# wrover-cam1.net
KiCad netlist of a schematic drawn in EAGLE
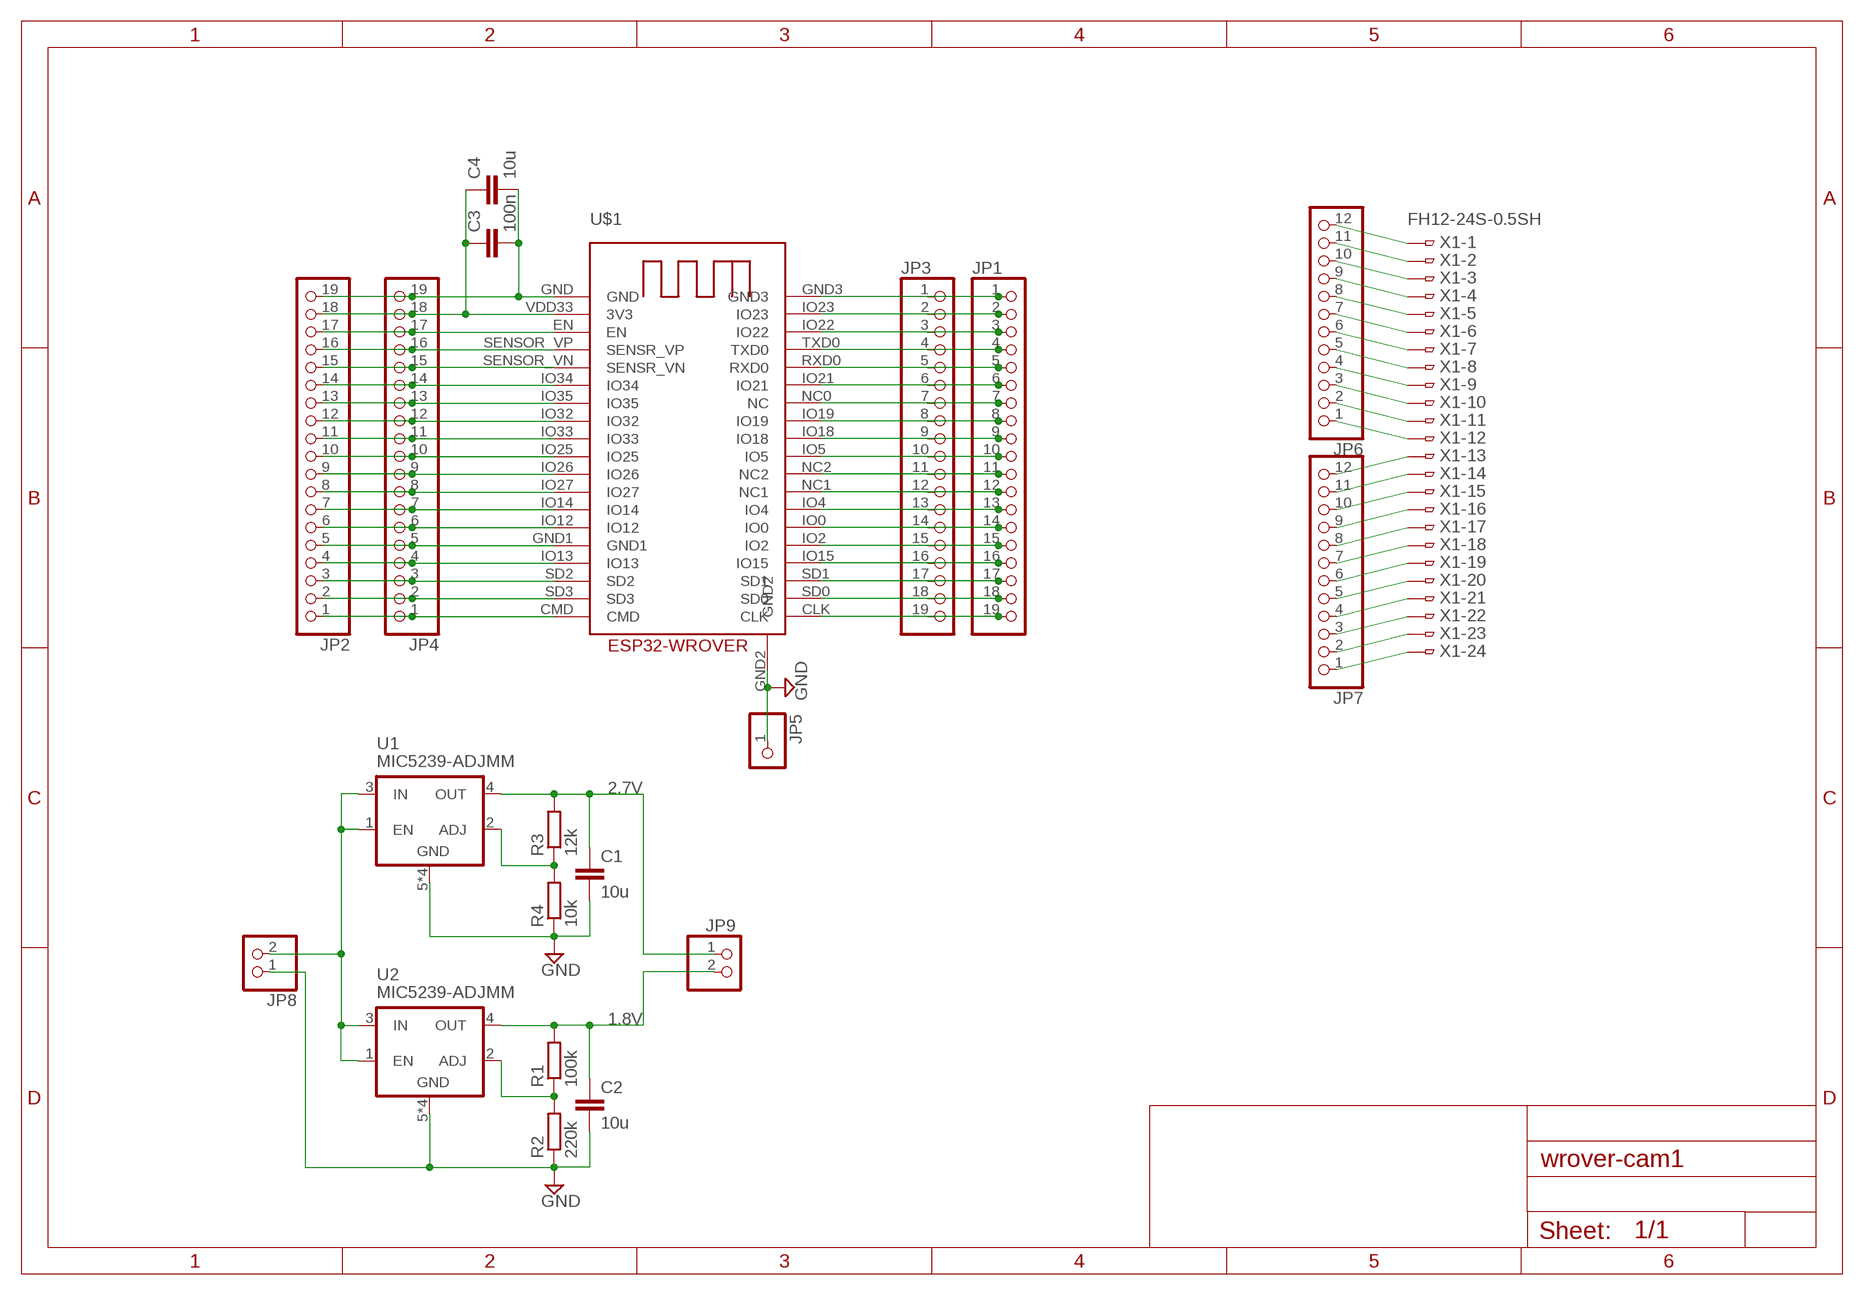
[diagram p0: schematic, sheet 1]

(export (version "E")
  (design (tool "Eeschema 10.0.6"))
  (components
    (comp (ref "C1")
      (value "10u")
      (footprint "eagle-import:C1210K")
      (libsource (lib "eagle-import") (part "C-EUC1210K"))
    )
    (comp (ref "C2")
      (value "10u")
      (footprint "eagle-import:C1210K")
      (libsource (lib "eagle-import") (part "C-EUC1210K"))
    )
    (comp (ref "C3")
      (value "100n")
      (footprint "eagle-import:C0805K")
      (libsource (lib "eagle-import") (part "C-EUC0805K"))
    )
    (comp (ref "C4")
      (value "10u")
      (footprint "eagle-import:C1210K")
      (libsource (lib "eagle-import") (part "C-EUC1210K"))
    )
    (comp (ref "JP1")
      (value "PINHD-1X19")
      (footprint "eagle-import:1X19")
      (libsource (lib "eagle-import") (part "PINHD-1X19"))
    )
    (comp (ref "JP2")
      (value "PINHD-1X19")
      (footprint "eagle-import:1X19")
      (libsource (lib "eagle-import") (part "PINHD-1X19"))
    )
    (comp (ref "JP3")
      (value "PINHD-1X19")
      (footprint "eagle-import:1X19")
      (libsource (lib "eagle-import") (part "PINHD-1X19"))
    )
    (comp (ref "JP4")
      (value "PINHD-1X19")
      (footprint "eagle-import:1X19")
      (libsource (lib "eagle-import") (part "PINHD-1X19"))
    )
    (comp (ref "JP5")
      (value "PINHD-1X1")
      (footprint "eagle-import:1X01")
      (libsource (lib "eagle-import") (part "PINHD-1X1"))
    )
    (comp (ref "JP6")
      (value "PINHD-1X12")
      (footprint "eagle-import:1X12")
      (libsource (lib "eagle-import") (part "PINHD-1X12"))
    )
    (comp (ref "JP7")
      (value "PINHD-1X12")
      (footprint "eagle-import:1X12")
      (libsource (lib "eagle-import") (part "PINHD-1X12"))
    )
    (comp (ref "JP8")
      (value "PINHD-1X2")
      (footprint "eagle-import:1X02")
      (libsource (lib "eagle-import") (part "PINHD-1X2"))
    )
    (comp (ref "JP9")
      (value "PINHD-1X2")
      (footprint "eagle-import:1X02")
      (libsource (lib "eagle-import") (part "PINHD-1X2"))
    )
    (comp (ref "R1")
      (value "100k")
      (footprint "eagle-import:R1206")
      (libsource (lib "eagle-import") (part "R-EU_R1206"))
    )
    (comp (ref "R2")
      (value "220k")
      (footprint "eagle-import:R1206")
      (libsource (lib "eagle-import") (part "R-EU_R1206"))
    )
    (comp (ref "R3")
      (value "12k")
      (footprint "eagle-import:R1206")
      (libsource (lib "eagle-import") (part "R-EU_R1206"))
    )
    (comp (ref "R4")
      (value "10k")
      (footprint "eagle-import:R1206")
      (libsource (lib "eagle-import") (part "R-EU_R1206"))
    )
    (comp (ref "U$1")
      (value "ESP32-WROVER")
      (footprint "eagle-import:ESP32-WROVER")
      (libsource (lib "eagle-import") (part "ESP32-WROVER"))
    )
    (comp (ref "U1")
      (value "MIC5239-ADJMM")
      (footprint "eagle-import:MSOP08")
      (libsource (lib "eagle-import") (part "MIC5239-ADJMM"))
    )
    (comp (ref "U2")
      (value "MIC5239-ADJMM")
      (footprint "eagle-import:MSOP08")
      (libsource (lib "eagle-import") (part "MIC5239-ADJMM"))
    )
    (comp (ref "X1")
      (value "FH12-24S-0.5SH")
      (footprint "eagle-import:FH12-24S-0.5SH")
      (fields (field (name "MPN") "FH12-24S-0.5SH(55)"))
      (libsource (lib "eagle-import") (part "FH12-24S-0.5SH"))
    )
  )
  (nets
    (net (code "1") (name "/1.8V") (class "Default")
      (node (ref "C2") (pin "1") (pinfunction "1_1") (pintype "passive"))
      (node (ref "JP9") (pin "2") (pinfunction "2_2") (pintype "passive"))
      (node (ref "R1") (pin "2") (pinfunction "2_2") (pintype "passive"))
      (node (ref "U2") (pin "4") (pinfunction "OUT_4") (pintype "passive"))
    )
    (net (code "2") (name "/2.7V") (class "Default")
      (node (ref "C1") (pin "1") (pinfunction "1_1") (pintype "passive"))
      (node (ref "JP9") (pin "1") (pinfunction "1_1") (pintype "passive"))
      (node (ref "R3") (pin "2") (pinfunction "2_2") (pintype "passive"))
      (node (ref "U1") (pin "4") (pinfunction "OUT_4") (pintype "passive"))
    )
    (net (code "3") (name "GND") (class "Default")
      (node (ref "C1") (pin "2") (pinfunction "2_2") (pintype "passive"))
      (node (ref "C2") (pin "2") (pinfunction "2_2") (pintype "passive"))
      (node (ref "JP5") (pin "1") (pinfunction "1_1") (pintype "passive"))
      (node (ref "JP8") (pin "1") (pinfunction "1_1") (pintype "passive"))
      (node (ref "R2") (pin "1") (pinfunction "1_1") (pintype "passive"))
      (node (ref "R4") (pin "1") (pinfunction "1_1") (pintype "passive"))
      (node (ref "U$1") (pin "GND2") (pinfunction "GND2_GND2") (pintype "bidirectional"))
      (node (ref "U1") (pin "5") (pinfunction "GND_5") (pintype "power_in"))
      (node (ref "U1") (pin "6") (pinfunction "GND_6") (pintype "power_in"))
      (node (ref "U1") (pin "7") (pinfunction "GND_7") (pintype "power_in"))
      (node (ref "U1") (pin "8") (pinfunction "GND_8") (pintype "power_in"))
      (node (ref "U2") (pin "5") (pinfunction "GND_5") (pintype "power_in"))
      (node (ref "U2") (pin "6") (pinfunction "GND_6") (pintype "power_in"))
      (node (ref "U2") (pin "7") (pinfunction "GND_7") (pintype "power_in"))
      (node (ref "U2") (pin "8") (pinfunction "GND_8") (pintype "power_in"))
    )
    (net (code "4") (name "Net-(C3-Pad2)") (class "Default")
      (node (ref "C3") (pin "2") (pinfunction "2_2") (pintype "passive"))
      (node (ref "C4") (pin "2") (pinfunction "2_2") (pintype "passive"))
      (node (ref "JP2") (pin "19") (pinfunction "19_19") (pintype "passive"))
      (node (ref "JP4") (pin "19") (pinfunction "19_19") (pintype "passive"))
      (node (ref "U$1") (pin "GND") (pinfunction "GND_GND") (pintype "bidirectional"))
    )
    (net (code "5") (name "Net-(JP1-Pad1)") (class "Default")
      (node (ref "JP1") (pin "1") (pinfunction "1_1") (pintype "passive"))
      (node (ref "JP3") (pin "1") (pinfunction "1_1") (pintype "passive"))
      (node (ref "U$1") (pin "GND3") (pinfunction "GND3_GND3") (pintype "bidirectional"))
    )
    (net (code "6") (name "Net-(JP1-Pad2)") (class "Default")
      (node (ref "JP1") (pin "2") (pinfunction "2_2") (pintype "passive"))
      (node (ref "JP3") (pin "2") (pinfunction "2_2") (pintype "passive"))
      (node (ref "U$1") (pin "IO23") (pinfunction "IO23_IO23") (pintype "bidirectional"))
    )
    (net (code "7") (name "Net-(JP1-Pad3)") (class "Default")
      (node (ref "JP1") (pin "3") (pinfunction "3_3") (pintype "passive"))
      (node (ref "JP3") (pin "3") (pinfunction "3_3") (pintype "passive"))
      (node (ref "U$1") (pin "IO22") (pinfunction "IO22_IO22") (pintype "bidirectional"))
    )
    (net (code "8") (name "Net-(JP1-Pad4)") (class "Default")
      (node (ref "JP1") (pin "4") (pinfunction "4_4") (pintype "passive"))
      (node (ref "JP3") (pin "4") (pinfunction "4_4") (pintype "passive"))
      (node (ref "U$1") (pin "TXD0") (pinfunction "TXD0_TXD0") (pintype "bidirectional"))
    )
    (net (code "9") (name "Net-(JP1-Pad5)") (class "Default")
      (node (ref "JP1") (pin "5") (pinfunction "5_5") (pintype "passive"))
      (node (ref "JP3") (pin "5") (pinfunction "5_5") (pintype "passive"))
      (node (ref "U$1") (pin "RXD0") (pinfunction "RXD0_RXD0") (pintype "bidirectional"))
    )
    (net (code "10") (name "Net-(JP1-Pad6)") (class "Default")
      (node (ref "JP1") (pin "6") (pinfunction "6_6") (pintype "passive"))
      (node (ref "JP3") (pin "6") (pinfunction "6_6") (pintype "passive"))
      (node (ref "U$1") (pin "IO21") (pinfunction "IO21_IO21") (pintype "bidirectional"))
    )
    (net (code "11") (name "Net-(JP1-Pad8)") (class "Default")
      (node (ref "JP1") (pin "8") (pinfunction "8_8") (pintype "passive"))
      (node (ref "JP3") (pin "8") (pinfunction "8_8") (pintype "passive"))
      (node (ref "U$1") (pin "IO19") (pinfunction "IO19_IO19") (pintype "bidirectional"))
    )
    (net (code "12") (name "Net-(JP1-Pad9)") (class "Default")
      (node (ref "JP1") (pin "9") (pinfunction "9_9") (pintype "passive"))
      (node (ref "JP3") (pin "9") (pinfunction "9_9") (pintype "passive"))
      (node (ref "U$1") (pin "IO18") (pinfunction "IO18_IO18") (pintype "bidirectional"))
    )
    (net (code "13") (name "Net-(JP1-Pad10)") (class "Default")
      (node (ref "JP1") (pin "10") (pinfunction "10_10") (pintype "passive"))
      (node (ref "JP3") (pin "10") (pinfunction "10_10") (pintype "passive"))
      (node (ref "U$1") (pin "IO5") (pinfunction "IO5_IO5") (pintype "bidirectional"))
    )
    (net (code "14") (name "Net-(JP1-Pad11)") (class "Default")
      (node (ref "JP1") (pin "11") (pinfunction "11_11") (pintype "passive"))
      (node (ref "JP3") (pin "11") (pinfunction "11_11") (pintype "passive"))
      (node (ref "U$1") (pin "NC2") (pinfunction "NC2_NC2") (pintype "bidirectional"))
    )
    (net (code "15") (name "Net-(JP1-Pad12)") (class "Default")
      (node (ref "JP1") (pin "12") (pinfunction "12_12") (pintype "passive"))
      (node (ref "JP3") (pin "12") (pinfunction "12_12") (pintype "passive"))
      (node (ref "U$1") (pin "NC1") (pinfunction "NC1_NC1") (pintype "bidirectional"))
    )
    (net (code "16") (name "Net-(JP1-Pad13)") (class "Default")
      (node (ref "JP1") (pin "13") (pinfunction "13_13") (pintype "passive"))
      (node (ref "JP3") (pin "13") (pinfunction "13_13") (pintype "passive"))
      (node (ref "U$1") (pin "IO4") (pinfunction "IO4_IO4") (pintype "bidirectional"))
    )
    (net (code "17") (name "Net-(JP1-Pad14)") (class "Default")
      (node (ref "JP1") (pin "14") (pinfunction "14_14") (pintype "passive"))
      (node (ref "JP3") (pin "14") (pinfunction "14_14") (pintype "passive"))
      (node (ref "U$1") (pin "IO0") (pinfunction "IO0_IO0") (pintype "bidirectional"))
    )
    (net (code "18") (name "Net-(JP1-Pad15)") (class "Default")
      (node (ref "JP1") (pin "15") (pinfunction "15_15") (pintype "passive"))
      (node (ref "JP3") (pin "15") (pinfunction "15_15") (pintype "passive"))
      (node (ref "U$1") (pin "IO2") (pinfunction "IO2_IO2") (pintype "bidirectional"))
    )
    (net (code "19") (name "Net-(JP1-Pad16)") (class "Default")
      (node (ref "JP1") (pin "16") (pinfunction "16_16") (pintype "passive"))
      (node (ref "JP3") (pin "16") (pinfunction "16_16") (pintype "passive"))
      (node (ref "U$1") (pin "IO15") (pinfunction "IO15_IO15") (pintype "bidirectional"))
    )
    (net (code "20") (name "Net-(JP1-Pad17)") (class "Default")
      (node (ref "JP1") (pin "17") (pinfunction "17_17") (pintype "passive"))
      (node (ref "JP3") (pin "17") (pinfunction "17_17") (pintype "passive"))
      (node (ref "U$1") (pin "SD1") (pinfunction "SD1_SD1") (pintype "bidirectional"))
    )
    (net (code "21") (name "Net-(JP1-Pad18)") (class "Default")
      (node (ref "JP1") (pin "18") (pinfunction "18_18") (pintype "passive"))
      (node (ref "JP3") (pin "18") (pinfunction "18_18") (pintype "passive"))
      (node (ref "U$1") (pin "SD0") (pinfunction "SD0_SD0") (pintype "bidirectional"))
    )
    (net (code "22") (name "Net-(JP1-Pad19)") (class "Default")
      (node (ref "JP1") (pin "19") (pinfunction "19_19") (pintype "passive"))
      (node (ref "JP3") (pin "19") (pinfunction "19_19") (pintype "passive"))
      (node (ref "U$1") (pin "CLK") (pinfunction "CLK_CLK") (pintype "bidirectional"))
    )
    (net (code "23") (name "Net-(JP2-Pad1)") (class "Default")
      (node (ref "JP2") (pin "1") (pinfunction "1_1") (pintype "passive"))
      (node (ref "JP4") (pin "1") (pinfunction "1_1") (pintype "passive"))
      (node (ref "U$1") (pin "CMD") (pinfunction "CMD_CMD") (pintype "bidirectional"))
    )
    (net (code "24") (name "Net-(JP2-Pad2)") (class "Default")
      (node (ref "JP2") (pin "2") (pinfunction "2_2") (pintype "passive"))
      (node (ref "JP4") (pin "2") (pinfunction "2_2") (pintype "passive"))
      (node (ref "U$1") (pin "SD3") (pinfunction "SD3_SD3") (pintype "bidirectional"))
    )
    (net (code "25") (name "Net-(JP2-Pad3)") (class "Default")
      (node (ref "JP2") (pin "3") (pinfunction "3_3") (pintype "passive"))
      (node (ref "JP4") (pin "3") (pinfunction "3_3") (pintype "passive"))
      (node (ref "U$1") (pin "SD2") (pinfunction "SD2_SD2") (pintype "bidirectional"))
    )
    (net (code "26") (name "Net-(JP2-Pad4)") (class "Default")
      (node (ref "JP2") (pin "4") (pinfunction "4_4") (pintype "passive"))
      (node (ref "JP4") (pin "4") (pinfunction "4_4") (pintype "passive"))
      (node (ref "U$1") (pin "IO13") (pinfunction "IO13_IO13") (pintype "bidirectional"))
    )
    (net (code "27") (name "Net-(JP2-Pad5)") (class "Default")
      (node (ref "JP2") (pin "5") (pinfunction "5_5") (pintype "passive"))
      (node (ref "JP4") (pin "5") (pinfunction "5_5") (pintype "passive"))
      (node (ref "U$1") (pin "GND1") (pinfunction "GND1_GND1") (pintype "bidirectional"))
    )
    (net (code "28") (name "Net-(JP2-Pad6)") (class "Default")
      (node (ref "JP2") (pin "6") (pinfunction "6_6") (pintype "passive"))
      (node (ref "JP4") (pin "6") (pinfunction "6_6") (pintype "passive"))
      (node (ref "U$1") (pin "IO12") (pinfunction "IO12_IO12") (pintype "bidirectional"))
    )
    (net (code "29") (name "Net-(JP2-Pad7)") (class "Default")
      (node (ref "JP2") (pin "7") (pinfunction "7_7") (pintype "passive"))
      (node (ref "JP4") (pin "7") (pinfunction "7_7") (pintype "passive"))
      (node (ref "U$1") (pin "IO14") (pinfunction "IO14_IO14") (pintype "bidirectional"))
    )
    (net (code "30") (name "Net-(JP2-Pad8)") (class "Default")
      (node (ref "JP2") (pin "8") (pinfunction "8_8") (pintype "passive"))
      (node (ref "JP4") (pin "8") (pinfunction "8_8") (pintype "passive"))
      (node (ref "U$1") (pin "IO27") (pinfunction "IO27_IO27") (pintype "bidirectional"))
    )
    (net (code "31") (name "Net-(JP2-Pad9)") (class "Default")
      (node (ref "JP2") (pin "9") (pinfunction "9_9") (pintype "passive"))
      (node (ref "JP4") (pin "9") (pinfunction "9_9") (pintype "passive"))
      (node (ref "U$1") (pin "IO26") (pinfunction "IO26_IO26") (pintype "bidirectional"))
    )
    (net (code "32") (name "Net-(JP2-Pad10)") (class "Default")
      (node (ref "JP2") (pin "10") (pinfunction "10_10") (pintype "passive"))
      (node (ref "JP4") (pin "10") (pinfunction "10_10") (pintype "passive"))
      (node (ref "U$1") (pin "IO25") (pinfunction "IO25_IO25") (pintype "bidirectional"))
    )
    (net (code "33") (name "Net-(JP2-Pad11)") (class "Default")
      (node (ref "JP2") (pin "11") (pinfunction "11_11") (pintype "passive"))
      (node (ref "JP4") (pin "11") (pinfunction "11_11") (pintype "passive"))
      (node (ref "U$1") (pin "IO33") (pinfunction "IO33_IO33") (pintype "bidirectional"))
    )
    (net (code "34") (name "Net-(JP2-Pad12)") (class "Default")
      (node (ref "JP2") (pin "12") (pinfunction "12_12") (pintype "passive"))
      (node (ref "JP4") (pin "12") (pinfunction "12_12") (pintype "passive"))
      (node (ref "U$1") (pin "IO32") (pinfunction "IO32_IO32") (pintype "bidirectional"))
    )
    (net (code "35") (name "Net-(JP2-Pad13)") (class "Default")
      (node (ref "JP2") (pin "13") (pinfunction "13_13") (pintype "passive"))
      (node (ref "JP4") (pin "13") (pinfunction "13_13") (pintype "passive"))
      (node (ref "U$1") (pin "IO35") (pinfunction "IO35_IO35") (pintype "bidirectional"))
    )
    (net (code "36") (name "Net-(JP2-Pad14)") (class "Default")
      (node (ref "JP2") (pin "14") (pinfunction "14_14") (pintype "passive"))
      (node (ref "JP4") (pin "14") (pinfunction "14_14") (pintype "passive"))
      (node (ref "U$1") (pin "IO34") (pinfunction "IO34_IO34") (pintype "bidirectional"))
    )
    (net (code "37") (name "Net-(JP2-Pad17)") (class "Default")
      (node (ref "JP2") (pin "17") (pinfunction "17_17") (pintype "passive"))
      (node (ref "JP4") (pin "17") (pinfunction "17_17") (pintype "passive"))
      (node (ref "U$1") (pin "EN") (pinfunction "EN_EN") (pintype "bidirectional"))
    )
    (net (code "38") (name "Net-(JP6-Pad12)") (class "Default")
      (node (ref "JP6") (pin "12") (pinfunction "12_12") (pintype "passive"))
      (node (ref "X1") (pin "1") (pinfunction "1_1") (pintype "passive"))
    )
    (net (code "39") (name "Net-(U$1-3V3)") (class "Default")
      (node (ref "C3") (pin "1") (pinfunction "1_1") (pintype "passive"))
      (node (ref "C4") (pin "1") (pinfunction "1_1") (pintype "passive"))
      (node (ref "JP2") (pin "18") (pinfunction "18_18") (pintype "passive"))
      (node (ref "JP4") (pin "18") (pinfunction "18_18") (pintype "passive"))
      (node (ref "U$1") (pin "VDD33") (pinfunction "3V3_VDD33") (pintype "bidirectional"))
    )
    (net (code "40") (name "Net-(U$1-NC)") (class "Default")
      (node (ref "JP1") (pin "7") (pinfunction "7_7") (pintype "passive"))
      (node (ref "JP3") (pin "7") (pinfunction "7_7") (pintype "passive"))
      (node (ref "U$1") (pin "NC0") (pinfunction "NC_NC0") (pintype "bidirectional"))
    )
    (net (code "41") (name "Net-(U$1-SENSR_VN)") (class "Default")
      (node (ref "JP2") (pin "15") (pinfunction "15_15") (pintype "passive"))
      (node (ref "JP4") (pin "15") (pinfunction "15_15") (pintype "passive"))
      (node (ref "U$1") (pin "SENSOR_VN") (pinfunction "SENSR_VN_SENSOR_VN") (pintype "bidirectional"))
    )
    (net (code "42") (name "Net-(U$1-SENSR_VP)") (class "Default")
      (node (ref "JP2") (pin "16") (pinfunction "16_16") (pintype "passive"))
      (node (ref "JP4") (pin "16") (pinfunction "16_16") (pintype "passive"))
      (node (ref "U$1") (pin "SENSOR_VP") (pinfunction "SENSR_VP_SENSOR_VP") (pintype "bidirectional"))
    )
    (net (code "43") (name "Net-(U1-ADJ)") (class "Default")
      (node (ref "R3") (pin "1") (pinfunction "1_1") (pintype "passive"))
      (node (ref "R4") (pin "2") (pinfunction "2_2") (pintype "passive"))
      (node (ref "U1") (pin "2") (pinfunction "ADJ_2") (pintype "passive"))
    )
    (net (code "44") (name "Net-(U1-EN)") (class "Default")
      (node (ref "JP8") (pin "2") (pinfunction "2_2") (pintype "passive"))
      (node (ref "U1") (pin "1") (pinfunction "EN_1") (pintype "input"))
      (node (ref "U1") (pin "3") (pinfunction "IN_3") (pintype "input"))
      (node (ref "U2") (pin "1") (pinfunction "EN_1") (pintype "input"))
      (node (ref "U2") (pin "3") (pinfunction "IN_3") (pintype "input"))
    )
    (net (code "45") (name "Net-(U2-ADJ)") (class "Default")
      (node (ref "R1") (pin "1") (pinfunction "1_1") (pintype "passive"))
      (node (ref "R2") (pin "2") (pinfunction "2_2") (pintype "passive"))
      (node (ref "U2") (pin "2") (pinfunction "ADJ_2") (pintype "passive"))
    )
    (net (code "46") (name "Net-(X1B-1)") (class "Default")
      (node (ref "JP6") (pin "3") (pinfunction "3_3") (pintype "passive"))
      (node (ref "X1") (pin "10") (pinfunction "1_10") (pintype "passive"))
    )
    (net (code "47") (name "Net-(X1C-1)") (class "Default")
      (node (ref "JP6") (pin "2") (pinfunction "2_2") (pintype "passive"))
      (node (ref "X1") (pin "11") (pinfunction "1_11") (pintype "passive"))
    )
    (net (code "48") (name "Net-(X1D-1)") (class "Default")
      (node (ref "JP6") (pin "1") (pinfunction "1_1") (pintype "passive"))
      (node (ref "X1") (pin "12") (pinfunction "1_12") (pintype "passive"))
    )
    (net (code "49") (name "Net-(X1E-1)") (class "Default")
      (node (ref "JP7") (pin "12") (pinfunction "12_12") (pintype "passive"))
      (node (ref "X1") (pin "13") (pinfunction "1_13") (pintype "passive"))
    )
    (net (code "50") (name "Net-(X1F-1)") (class "Default")
      (node (ref "JP7") (pin "11") (pinfunction "11_11") (pintype "passive"))
      (node (ref "X1") (pin "14") (pinfunction "1_14") (pintype "passive"))
    )
    (net (code "51") (name "Net-(X1G-1)") (class "Default")
      (node (ref "JP7") (pin "10") (pinfunction "10_10") (pintype "passive"))
      (node (ref "X1") (pin "15") (pinfunction "1_15") (pintype "passive"))
    )
    (net (code "52") (name "Net-(X1H-1)") (class "Default")
      (node (ref "JP7") (pin "9") (pinfunction "9_9") (pintype "passive"))
      (node (ref "X1") (pin "16") (pinfunction "1_16") (pintype "passive"))
    )
    (net (code "53") (name "Net-(X1I-1)") (class "Default")
      (node (ref "JP7") (pin "8") (pinfunction "8_8") (pintype "passive"))
      (node (ref "X1") (pin "17") (pinfunction "1_17") (pintype "passive"))
    )
    (net (code "54") (name "Net-(X1J-1)") (class "Default")
      (node (ref "JP7") (pin "7") (pinfunction "7_7") (pintype "passive"))
      (node (ref "X1") (pin "18") (pinfunction "1_18") (pintype "passive"))
    )
    (net (code "55") (name "Net-(X1K-1)") (class "Default")
      (node (ref "JP7") (pin "6") (pinfunction "6_6") (pintype "passive"))
      (node (ref "X1") (pin "19") (pinfunction "1_19") (pintype "passive"))
    )
    (net (code "56") (name "Net-(X1L-1)") (class "Default")
      (node (ref "JP6") (pin "11") (pinfunction "11_11") (pintype "passive"))
      (node (ref "X1") (pin "2") (pinfunction "1_2") (pintype "passive"))
    )
    (net (code "57") (name "Net-(X1M-1)") (class "Default")
      (node (ref "JP7") (pin "5") (pinfunction "5_5") (pintype "passive"))
      (node (ref "X1") (pin "20") (pinfunction "1_20") (pintype "passive"))
    )
    (net (code "58") (name "Net-(X1N-1)") (class "Default")
      (node (ref "JP7") (pin "4") (pinfunction "4_4") (pintype "passive"))
      (node (ref "X1") (pin "21") (pinfunction "1_21") (pintype "passive"))
    )
    (net (code "59") (name "Net-(X1O-1)") (class "Default")
      (node (ref "JP7") (pin "3") (pinfunction "3_3") (pintype "passive"))
      (node (ref "X1") (pin "22") (pinfunction "1_22") (pintype "passive"))
    )
    (net (code "60") (name "Net-(X1P-1)") (class "Default")
      (node (ref "JP7") (pin "2") (pinfunction "2_2") (pintype "passive"))
      (node (ref "X1") (pin "23") (pinfunction "1_23") (pintype "passive"))
    )
    (net (code "61") (name "Net-(X1Q-1)") (class "Default")
      (node (ref "JP7") (pin "1") (pinfunction "1_1") (pintype "passive"))
      (node (ref "X1") (pin "24") (pinfunction "1_24") (pintype "passive"))
    )
    (net (code "62") (name "Net-(X1R-1)") (class "Default")
      (node (ref "JP6") (pin "10") (pinfunction "10_10") (pintype "passive"))
      (node (ref "X1") (pin "3") (pinfunction "1_3") (pintype "passive"))
    )
    (net (code "63") (name "Net-(X1S-1)") (class "Default")
      (node (ref "JP6") (pin "9") (pinfunction "9_9") (pintype "passive"))
      (node (ref "X1") (pin "4") (pinfunction "1_4") (pintype "passive"))
    )
    (net (code "64") (name "Net-(X1T-1)") (class "Default")
      (node (ref "JP6") (pin "8") (pinfunction "8_8") (pintype "passive"))
      (node (ref "X1") (pin "5") (pinfunction "1_5") (pintype "passive"))
    )
    (net (code "65") (name "Net-(X1U-1)") (class "Default")
      (node (ref "JP6") (pin "7") (pinfunction "7_7") (pintype "passive"))
      (node (ref "X1") (pin "6") (pinfunction "1_6") (pintype "passive"))
    )
    (net (code "66") (name "Net-(X1V-1)") (class "Default")
      (node (ref "JP6") (pin "6") (pinfunction "6_6") (pintype "passive"))
      (node (ref "X1") (pin "7") (pinfunction "1_7") (pintype "passive"))
    )
    (net (code "67") (name "Net-(X1W-1)") (class "Default")
      (node (ref "JP6") (pin "5") (pinfunction "5_5") (pintype "passive"))
      (node (ref "X1") (pin "8") (pinfunction "1_8") (pintype "passive"))
    )
    (net (code "68") (name "Net-(X1X-1)") (class "Default")
      (node (ref "JP6") (pin "4") (pinfunction "4_4") (pintype "passive"))
      (node (ref "X1") (pin "9") (pinfunction "1_9") (pintype "passive"))
    )
  )
)
